# 02-MCU.net
KiCad netlist of a schematic drawn in Altium Designer
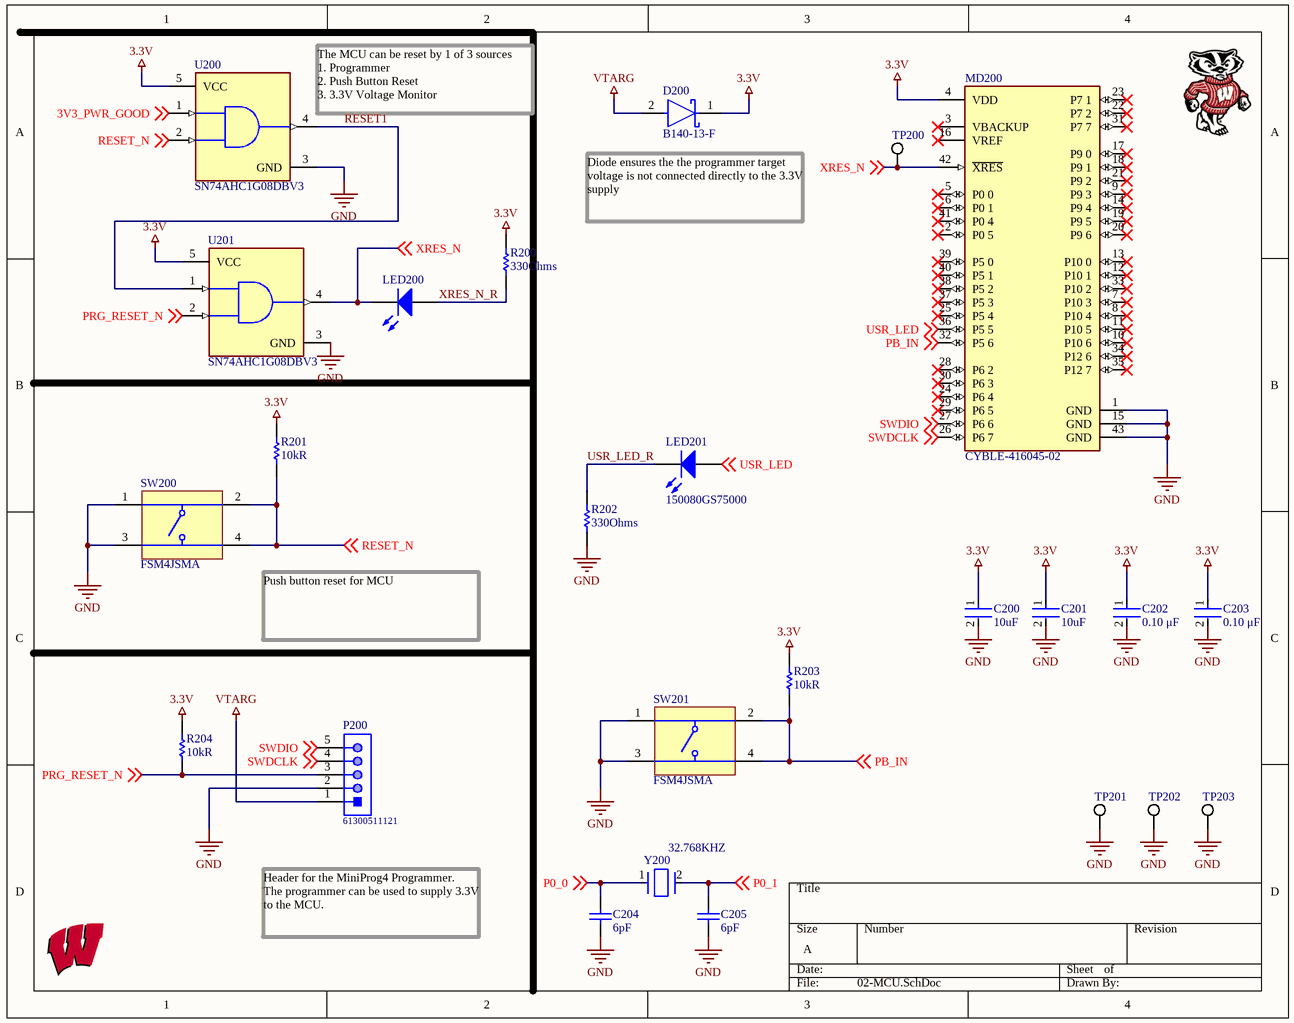
[diagram p0: 02-MCU.SchDoc]

(export (version "E")
  (design (tool "Eeschema 10.0.6"))
  (components
    (comp (ref "C200")
      (value "10uF")
      (footprint "FP-C0805C-DG-MFG")
      (description "CAP CER 10UF 10V X5R 0805")
      (fields (field (name "TOLERANCE") "10%") (field (name "MANUFACTURER PART NUMBER") "C0805C106K8PACTU"))
      (libsource (lib "Altium Content Vault") (part "11868f565c42a9108669ba33697ecf6"))
    )
    (comp (ref "C201")
      (value "10uF")
      (footprint "FP-C0805C-DG-MFG")
      (description "CAP CER 10UF 10V X5R 0805")
      (fields (field (name "TOLERANCE") "10%") (field (name "MANUFACTURER PART NUMBER") "C0805C106K8PACTU"))
      (libsource (lib "Altium Content Vault") (part "11868f565c42a9108669ba33697ecf6"))
    )
    (comp (ref "C202")
      (value "0.10 μF")
      (footprint "FP-C0805C-DN-MFG")
      (description "CAP CER 0.1UF 50V X7R 0805")
      (fields
        (field (name "MANUFACTURER PART NUMBER") "C0805C104K5RACTU")
        (field (name "MANUFACTURER") "KEMET")
      )
      (libsource (lib "Altium Content Vault") (part "b4654b650e69147ec39a6b967a45e02"))
    )
    (comp (ref "C203")
      (value "0.10 μF")
      (footprint "FP-C0805C-DN-MFG")
      (description "CAP CER 0.1UF 50V X7R 0805")
      (fields
        (field (name "MANUFACTURER PART NUMBER") "C0805C104K5RACTU")
        (field (name "MANUFACTURER") "KEMET")
      )
      (libsource (lib "Altium Content Vault") (part "b4654b650e69147ec39a6b967a45e02"))
    )
    (comp (ref "C204")
      (value "08055A6R0CAT2A")
      (footprint "CAPC2013X94X50LL20T25")
      (fields (field (name "MANUFACTURER") "AVX Interconnect / Elco") (field (name "CAPACITANCE") "6pF"))
      (libsource (lib "Altium Content Vault") (part "CAP"))
    )
    (comp (ref "C205")
      (value "08055A6R0CAT2A")
      (footprint "CAPC2013X94X50LL20T25")
      (fields (field (name "MANUFACTURER") "AVX Interconnect / Elco") (field (name "CAPACITANCE") "6pF"))
      (libsource (lib "Altium Content Vault") (part "CAP"))
    )
    (comp (ref "D200")
      (value "B140-13-F")
      (footprint "FP-SMA-MFG")
      (description "DIODE SCHOTTKY 40V 1A SMA")
      (libsource (lib "Altium Content Vault") (part "1d6ec82d83fb6aee721767c19dac4b9"))
    )
    (comp (ref "LED200")
      (value "150080RS75000")
      (footprint "0805_A")
      (description "SMD mono-color Chip LED, WL-SMCW, Red")
      (fields (field (name "MANUFACTURER") "Wuerth Elektronik"))
      (libsource (lib "Altium Content Vault") (part "WE-LED_K1A2-2"))
    )
    (comp (ref "LED201")
      (value "150080GS75000")
      (footprint "0805_A")
      (description "SMD mono-color Chip LED, WL-SMCW, Green")
      (fields (field (name "MANUFACTURER") "Wuerth Elektronik"))
      (libsource (lib "Altium Content Vault") (part "WE-LED_K1A2-2"))
    )
    (comp (ref "MD200")
      (value "CYBLE-416045-02")
      (footprint "FP-CYBLE-416045-02-MFG")
      (description "RF TXRX MOD BLUETOOTH TRACE ANT")
      (fields
        (field (name "OCTOPART") "https://octopart.com/cyble-416045-02-cypress+semiconductor-96386825")
        (field (name "MANUFACTURER") "Cypress Semiconductor")
      )
      (libsource (lib "Altium Content Vault") (part "10a29a4e77099fbb6f911efb04878b1"))
    )
    (comp (ref "P200")
      (value "61300511121")
      (footprint "61300511121")
      (description "THT Vertical Pin Header WR-PHD, Pitch 2.54 mm, Single Row, 5 pins")
      (fields (field (name "MANUFACTURER") "Wurth Elektronik") (field (name "PUBLISHER") "WurthElektronik"))
      (libsource (lib "Altium Content Vault") (part "WE-CN-1P-M-R5"))
    )
    (comp (ref "R200")
      (value "RC0805FR-07330RL")
      (footprint "RESC2013X60X35LL10T20")
      (description "Chip Resistor, 330 Ohm, +/- 1%, 125 mW, -55 to 155 degC, 0805 (2012 Metric), RoHS, Tape and Reel")
      (fields
        (field (name "MANUFACTURER") "Yageo")
        (field (name "TOLERANCE") "1%")
        (field (name "RESISTANCE") "330Ohms")
      )
      (libsource (lib "Altium Content Vault") (part "RES-2"))
    )
    (comp (ref "R201")
      (value "RC0805FR-0710KL")
      (footprint "RESC2013X60X35NL10T20")
      (description "Chip Resistor, 10 KOhm, +/- 1%, 0.125 W, -55 to 155 degC, 0805 (2012 Metric), RoHS, Tape and Reel")
      (fields
        (field (name "MANUFACTURER") "Yageo")
        (field (name "RESISTANCE") "10kR")
        (field (name "TOLERANCE") "1%")
      )
      (libsource (lib "Altium Content Vault") (part "RES-2"))
    )
    (comp (ref "R202")
      (value "RC0805FR-07330RL")
      (footprint "RESC2013X60X35LL10T20")
      (description "Chip Resistor, 330 Ohm, +/- 1%, 125 mW, -55 to 155 degC, 0805 (2012 Metric), RoHS, Tape and Reel")
      (fields
        (field (name "MANUFACTURER") "Yageo")
        (field (name "TOLERANCE") "1%")
        (field (name "RESISTANCE") "330Ohms")
      )
      (libsource (lib "Altium Content Vault") (part "RES-2"))
    )
    (comp (ref "R203")
      (value "RC0805FR-0710KL")
      (footprint "RESC2013X60X35NL10T20")
      (description "Chip Resistor, 10 KOhm, +/- 1%, 0.125 W, -55 to 155 degC, 0805 (2012 Metric), RoHS, Tape and Reel")
      (fields
        (field (name "MANUFACTURER") "Yageo")
        (field (name "RESISTANCE") "10kR")
        (field (name "TOLERANCE") "1%")
      )
      (libsource (lib "Altium Content Vault") (part "RES-2"))
    )
    (comp (ref "R204")
      (value "RC0805FR-0710KL")
      (footprint "RESC2013X60X35NL10T20")
      (description "Chip Resistor, 10 KOhm, +/- 1%, 0.125 W, -55 to 155 degC, 0805 (2012 Metric), RoHS, Tape and Reel")
      (fields
        (field (name "MANUFACTURER") "Yageo")
        (field (name "RESISTANCE") "10kR")
        (field (name "TOLERANCE") "1%")
      )
      (libsource (lib "Altium Content Vault") (part "RES-2"))
    )
    (comp (ref "SW200")
      (value "FSM4JSMA")
      (footprint "TECO-FSM4JSMA_V")
      (description "Swicth, SPST, 24 V, -35 to 85 degC, 4-Pin SMD, RoHS, Tape and Reel")
      (fields (field (name "MANUFACTURER") "TE Connectivity"))
      (libsource (lib "Altium Content Vault") (part "SW-SPST-4_A"))
    )
    (comp (ref "SW201")
      (value "FSM4JSMA")
      (footprint "TECO-FSM4JSMA_V")
      (description "Swicth, SPST, 24 V, -35 to 85 degC, 4-Pin SMD, RoHS, Tape and Reel")
      (fields (field (name "MANUFACTURER") "TE Connectivity"))
      (libsource (lib "Altium Content Vault") (part "SW-SPST-4_A"))
    )
    (comp (ref "TP200")
      (value "5019")
      (footprint "KSTN-5019_V")
      (description "Test Point, 1 Position SMD, RoHS, Tape and Reel")
      (libsource (lib "Altium Content Vault") (part "TESTPOINT_WHITE"))
    )
    (comp (ref "TP201")
      (value "5019")
      (footprint "KSTN-5019_V")
      (description "Test Point, 1 Position SMD, RoHS, Tape and Reel")
      (libsource (lib "Altium Content Vault") (part "TESTPOINT_WHITE"))
    )
    (comp (ref "TP202")
      (value "5019")
      (footprint "KSTN-5019_V")
      (description "Test Point, 1 Position SMD, RoHS, Tape and Reel")
      (libsource (lib "Altium Content Vault") (part "TESTPOINT_WHITE"))
    )
    (comp (ref "TP203")
      (value "5019")
      (footprint "KSTN-5019_V")
      (description "Test Point, 1 Position SMD, RoHS, Tape and Reel")
      (libsource (lib "Altium Content Vault") (part "TESTPOINT_WHITE"))
    )
    (comp (ref "U200")
      (value "SN74AHC1G08DBV3")
      (footprint "FP-DBV0005A-IPC_C")
      (description "IC GATE AND 1CH 2-INP SOT23-5")
      (libsource (lib "Altium Content Vault") (part "675e79b427d6219a5295bf943425e1c"))
    )
    (comp (ref "U201")
      (value "SN74AHC1G08DBV3")
      (footprint "FP-DBV0005A-IPC_C")
      (description "IC GATE AND 1CH 2-INP SOT23-5")
      (libsource (lib "Altium Content Vault") (part "675e79b427d6219a5295bf943425e1c"))
    )
    (comp (ref "Y200")
      (value "32.768KHZ")
      (footprint "FP-ABS07-120-MFG")
      (description "CRYSTAL 32.7680KHZ 6PF SMD")
      (fields (field (name "TOLERANCE") "20ppm"))
      (libsource (lib "Altium Content Vault") (part "c23a69dc6c9e2f18f2079038eb95dd1"))
    )
  )
  (nets
    (net (code "1") (name "/RESET1") (class "Default")
      (node (ref "U200") (pin "4") (pinfunction "Y_4") (pintype "output"))
      (node (ref "U201") (pin "1") (pinfunction "A_1") (pintype "input"))
    )
    (net (code "2") (name "/USR_LED_R") (class "Default")
      (node (ref "LED201") (pin "1") (pinfunction "K_1") (pintype "passive"))
      (node (ref "R202") (pin "2") (pinfunction "2_2") (pintype "passive"))
    )
    (net (code "3") (name "/XRES_N_R") (class "Default")
      (node (ref "LED200") (pin "2") (pinfunction "A_2") (pintype "passive"))
      (node (ref "R200") (pin "1") (pinfunction "1_1") (pintype "passive"))
    )
    (net (code "4") (name "3.3V") (class "Default")
      (node (ref "C200") (pin "1") (pinfunction "1_1") (pintype "passive"))
      (node (ref "C201") (pin "1") (pinfunction "1_1") (pintype "passive"))
      (node (ref "C202") (pin "1") (pinfunction "1_1") (pintype "passive"))
      (node (ref "C203") (pin "1") (pinfunction "1_1") (pintype "passive"))
      (node (ref "D200") (pin "1") (pinfunction "C_1") (pintype "passive"))
      (node (ref "MD200") (pin "4") (pinfunction "VDD_4") (pintype "power_in"))
      (node (ref "R200") (pin "2") (pinfunction "2_2") (pintype "passive"))
      (node (ref "R201") (pin "2") (pinfunction "2_2") (pintype "passive"))
      (node (ref "R203") (pin "2") (pinfunction "2_2") (pintype "passive"))
      (node (ref "R204") (pin "2") (pinfunction "2_2") (pintype "passive"))
      (node (ref "U200") (pin "5") (pinfunction "VCC_5") (pintype "power_in"))
      (node (ref "U201") (pin "5") (pinfunction "VCC_5") (pintype "power_in"))
    )
    (net (code "5") (name "3V3_PWR_GOOD") (class "Default")
      (node (ref "U200") (pin "1") (pinfunction "A_1") (pintype "input"))
    )
    (net (code "6") (name "GND") (class "Default")
      (node (ref "C200") (pin "2") (pinfunction "2_2") (pintype "passive"))
      (node (ref "C201") (pin "2") (pinfunction "2_2") (pintype "passive"))
      (node (ref "C202") (pin "2") (pinfunction "2_2") (pintype "passive"))
      (node (ref "C203") (pin "2") (pinfunction "2_2") (pintype "passive"))
      (node (ref "C204") (pin "1") (pinfunction "1_1") (pintype "passive"))
      (node (ref "C205") (pin "1") (pinfunction "1_1") (pintype "passive"))
      (node (ref "MD200") (pin "1") (pinfunction "GND_1") (pintype "power_in"))
      (node (ref "MD200") (pin "15") (pinfunction "GND_15") (pintype "power_in"))
      (node (ref "MD200") (pin "43") (pinfunction "GND_43") (pintype "power_in"))
      (node (ref "P200") (pin "2") (pinfunction "2_2") (pintype "passive"))
      (node (ref "R202") (pin "1") (pinfunction "1_1") (pintype "passive"))
      (node (ref "SW200") (pin "1") (pinfunction "1_1") (pintype "passive"))
      (node (ref "SW200") (pin "3") (pinfunction "3_3") (pintype "passive"))
      (node (ref "SW201") (pin "1") (pinfunction "1_1") (pintype "passive"))
      (node (ref "SW201") (pin "3") (pinfunction "3_3") (pintype "passive"))
      (node (ref "TP201") (pin "1") (pinfunction "1_1") (pintype "passive"))
      (node (ref "TP202") (pin "1") (pinfunction "1_1") (pintype "passive"))
      (node (ref "TP203") (pin "1") (pinfunction "1_1") (pintype "passive"))
      (node (ref "U200") (pin "3") (pinfunction "GND_3") (pintype "power_in"))
      (node (ref "U201") (pin "3") (pinfunction "GND_3") (pintype "power_in"))
    )
    (net (code "7") (name "P0_0") (class "Default")
      (node (ref "C204") (pin "2") (pinfunction "2_2") (pintype "passive"))
      (node (ref "Y200") (pin "1") (pinfunction "1_1") (pintype "passive"))
    )
    (net (code "8") (name "P0_1") (class "Default")
      (node (ref "C205") (pin "2") (pinfunction "2_2") (pintype "passive"))
      (node (ref "Y200") (pin "2") (pinfunction "2_2") (pintype "passive"))
    )
    (net (code "9") (name "PB_IN") (class "Default")
      (node (ref "MD200") (pin "32") (pinfunction "P5_6_32") (pintype "bidirectional"))
      (node (ref "R203") (pin "1") (pinfunction "1_1") (pintype "passive"))
      (node (ref "SW201") (pin "2") (pinfunction "2_2") (pintype "passive"))
      (node (ref "SW201") (pin "4") (pinfunction "4_4") (pintype "passive"))
    )
    (net (code "10") (name "PRG_RESET_N") (class "Default")
      (node (ref "P200") (pin "3") (pinfunction "3_3") (pintype "passive"))
      (node (ref "R204") (pin "1") (pinfunction "1_1") (pintype "passive"))
      (node (ref "U201") (pin "2") (pinfunction "B_2") (pintype "input"))
    )
    (net (code "11") (name "RESET_N") (class "Default")
      (node (ref "R201") (pin "1") (pinfunction "1_1") (pintype "passive"))
      (node (ref "SW200") (pin "2") (pinfunction "2_2") (pintype "passive"))
      (node (ref "SW200") (pin "4") (pinfunction "4_4") (pintype "passive"))
      (node (ref "U200") (pin "2") (pinfunction "B_2") (pintype "input"))
    )
    (net (code "12") (name "SWDCLK") (class "Default")
      (node (ref "MD200") (pin "26") (pinfunction "P6_7_26") (pintype "bidirectional"))
      (node (ref "P200") (pin "4") (pinfunction "4_4") (pintype "passive"))
    )
    (net (code "13") (name "SWDIO") (class "Default")
      (node (ref "MD200") (pin "27") (pinfunction "P6_6_27") (pintype "bidirectional"))
      (node (ref "P200") (pin "5") (pinfunction "5_5") (pintype "passive"))
    )
    (net (code "14") (name "USR_LED") (class "Default")
      (node (ref "LED201") (pin "2") (pinfunction "A_2") (pintype "passive"))
      (node (ref "MD200") (pin "36") (pinfunction "P5_5_36") (pintype "bidirectional"))
    )
    (net (code "15") (name "VTARG") (class "Default")
      (node (ref "D200") (pin "2") (pinfunction "A_2") (pintype "passive"))
      (node (ref "P200") (pin "1") (pinfunction "1_1") (pintype "passive"))
    )
    (net (code "16") (name "XRES_N") (class "Default")
      (node (ref "LED200") (pin "1") (pinfunction "K_1") (pintype "passive"))
      (node (ref "MD200") (pin "42") (pinfunction "~{XRES}_42") (pintype "input"))
      (node (ref "TP200") (pin "1") (pinfunction "1_1") (pintype "passive"))
      (node (ref "U201") (pin "4") (pinfunction "Y_4") (pintype "output"))
    )
    (net (code "17") (name "unconnected-(MD200-P0_0-Pad5)") (class "Default")
      (node (ref "MD200") (pin "5") (pinfunction "P0_0_5") (pintype "bidirectional+no_connect"))
    )
    (net (code "18") (name "unconnected-(MD200-P0_1-Pad6)") (class "Default")
      (node (ref "MD200") (pin "6") (pinfunction "P0_1_6") (pintype "bidirectional+no_connect"))
    )
    (net (code "19") (name "unconnected-(MD200-P0_4-Pad41)") (class "Default")
      (node (ref "MD200") (pin "41") (pinfunction "P0_4_41") (pintype "bidirectional+no_connect"))
    )
    (net (code "20") (name "unconnected-(MD200-P0_5-Pad2)") (class "Default")
      (node (ref "MD200") (pin "2") (pinfunction "P0_5_2") (pintype "bidirectional+no_connect"))
    )
    (net (code "21") (name "unconnected-(MD200-P5_0-Pad39)") (class "Default")
      (node (ref "MD200") (pin "39") (pinfunction "P5_0_39") (pintype "bidirectional+no_connect"))
    )
    (net (code "22") (name "unconnected-(MD200-P5_1-Pad40)") (class "Default")
      (node (ref "MD200") (pin "40") (pinfunction "P5_1_40") (pintype "bidirectional+no_connect"))
    )
    (net (code "23") (name "unconnected-(MD200-P5_2-Pad38)") (class "Default")
      (node (ref "MD200") (pin "38") (pinfunction "P5_2_38") (pintype "bidirectional+no_connect"))
    )
    (net (code "24") (name "unconnected-(MD200-P5_3-Pad37)") (class "Default")
      (node (ref "MD200") (pin "37") (pinfunction "P5_3_37") (pintype "bidirectional+no_connect"))
    )
    (net (code "25") (name "unconnected-(MD200-P5_4-Pad25)") (class "Default")
      (node (ref "MD200") (pin "25") (pinfunction "P5_4_25") (pintype "bidirectional+no_connect"))
    )
    (net (code "26") (name "unconnected-(MD200-P6_2-Pad28)") (class "Default")
      (node (ref "MD200") (pin "28") (pinfunction "P6_2_28") (pintype "bidirectional+no_connect"))
    )
    (net (code "27") (name "unconnected-(MD200-P6_3-Pad30)") (class "Default")
      (node (ref "MD200") (pin "30") (pinfunction "P6_3_30") (pintype "bidirectional+no_connect"))
    )
    (net (code "28") (name "unconnected-(MD200-P6_4-Pad24)") (class "Default")
      (node (ref "MD200") (pin "24") (pinfunction "P6_4_24") (pintype "bidirectional+no_connect"))
    )
    (net (code "29") (name "unconnected-(MD200-P6_5-Pad29)") (class "Default")
      (node (ref "MD200") (pin "29") (pinfunction "P6_5_29") (pintype "bidirectional+no_connect"))
    )
    (net (code "30") (name "unconnected-(MD200-P7_1-Pad23)") (class "Default")
      (node (ref "MD200") (pin "23") (pinfunction "P7_1_23") (pintype "bidirectional+no_connect"))
    )
    (net (code "31") (name "unconnected-(MD200-P7_2-Pad22)") (class "Default")
      (node (ref "MD200") (pin "22") (pinfunction "P7_2_22") (pintype "bidirectional+no_connect"))
    )
    (net (code "32") (name "unconnected-(MD200-P7_7-Pad31)") (class "Default")
      (node (ref "MD200") (pin "31") (pinfunction "P7_7_31") (pintype "bidirectional+no_connect"))
    )
    (net (code "33") (name "unconnected-(MD200-P9_0-Pad17)") (class "Default")
      (node (ref "MD200") (pin "17") (pinfunction "P9_0_17") (pintype "bidirectional+no_connect"))
    )
    (net (code "34") (name "unconnected-(MD200-P9_1-Pad18)") (class "Default")
      (node (ref "MD200") (pin "18") (pinfunction "P9_1_18") (pintype "bidirectional+no_connect"))
    )
    (net (code "35") (name "unconnected-(MD200-P9_2-Pad21)") (class "Default")
      (node (ref "MD200") (pin "21") (pinfunction "P9_2_21") (pintype "bidirectional+no_connect"))
    )
    (net (code "36") (name "unconnected-(MD200-P9_3-Pad9)") (class "Default")
      (node (ref "MD200") (pin "9") (pinfunction "P9_3_9") (pintype "bidirectional+no_connect"))
    )
    (net (code "37") (name "unconnected-(MD200-P9_4-Pad14)") (class "Default")
      (node (ref "MD200") (pin "14") (pinfunction "P9_4_14") (pintype "bidirectional+no_connect"))
    )
    (net (code "38") (name "unconnected-(MD200-P9_5-Pad19)") (class "Default")
      (node (ref "MD200") (pin "19") (pinfunction "P9_5_19") (pintype "bidirectional+no_connect"))
    )
    (net (code "39") (name "unconnected-(MD200-P9_6-Pad20)") (class "Default")
      (node (ref "MD200") (pin "20") (pinfunction "P9_6_20") (pintype "bidirectional+no_connect"))
    )
    (net (code "40") (name "unconnected-(MD200-P10_0-Pad13)") (class "Default")
      (node (ref "MD200") (pin "13") (pinfunction "P10_0_13") (pintype "bidirectional+no_connect"))
    )
    (net (code "41") (name "unconnected-(MD200-P10_1-Pad12)") (class "Default")
      (node (ref "MD200") (pin "12") (pinfunction "P10_1_12") (pintype "bidirectional+no_connect"))
    )
    (net (code "42") (name "unconnected-(MD200-P10_2-Pad33)") (class "Default")
      (node (ref "MD200") (pin "33") (pinfunction "P10_2_33") (pintype "bidirectional+no_connect"))
    )
    (net (code "43") (name "unconnected-(MD200-P10_3-Pad7)") (class "Default")
      (node (ref "MD200") (pin "7") (pinfunction "P10_3_7") (pintype "bidirectional+no_connect"))
    )
    (net (code "44") (name "unconnected-(MD200-P10_4-Pad8)") (class "Default")
      (node (ref "MD200") (pin "8") (pinfunction "P10_4_8") (pintype "bidirectional+no_connect"))
    )
    (net (code "45") (name "unconnected-(MD200-P10_5-Pad11)") (class "Default")
      (node (ref "MD200") (pin "11") (pinfunction "P10_5_11") (pintype "bidirectional+no_connect"))
    )
    (net (code "46") (name "unconnected-(MD200-P10_6-Pad10)") (class "Default")
      (node (ref "MD200") (pin "10") (pinfunction "P10_6_10") (pintype "bidirectional+no_connect"))
    )
    (net (code "47") (name "unconnected-(MD200-P12_6-Pad34)") (class "Default")
      (node (ref "MD200") (pin "34") (pinfunction "P12_6_34") (pintype "bidirectional+no_connect"))
    )
    (net (code "48") (name "unconnected-(MD200-P12_7-Pad35)") (class "Default")
      (node (ref "MD200") (pin "35") (pinfunction "P12_7_35") (pintype "bidirectional+no_connect"))
    )
    (net (code "49") (name "unconnected-(MD200-VBACKUP-Pad3)") (class "Default")
      (node (ref "MD200") (pin "3") (pinfunction "VBACKUP_3") (pintype "power_in+no_connect"))
    )
    (net (code "50") (name "unconnected-(MD200-VREF-Pad16)") (class "Default")
      (node (ref "MD200") (pin "16") (pinfunction "VREF_16") (pintype "power_in+no_connect"))
    )
  )
)
